# supply.net
KiCad netlist of a schematic drawn in EAGLE
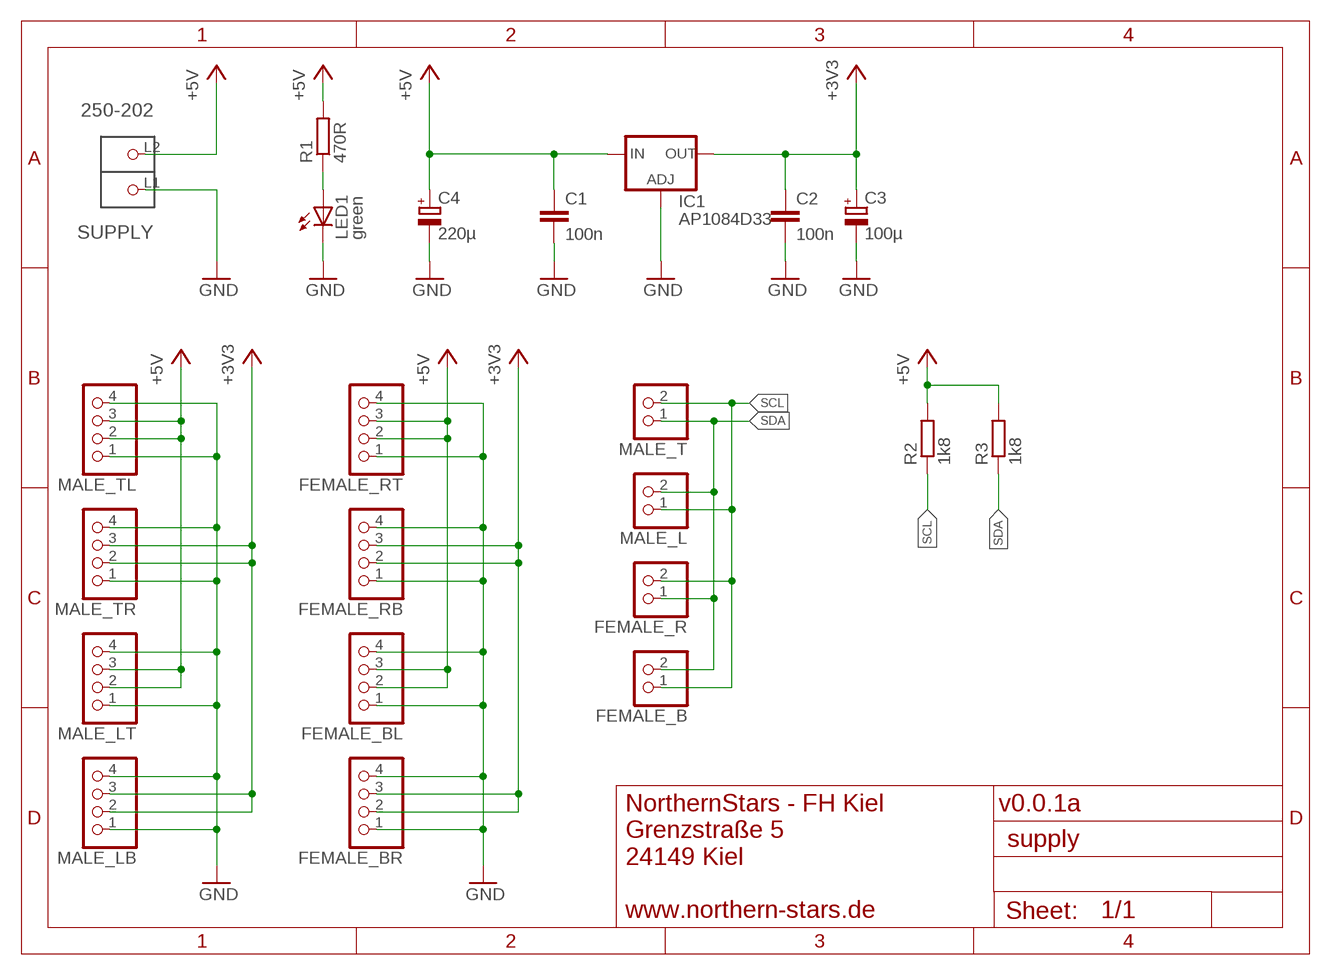
[diagram p0: schematic, sheet 1]

(export (version "E")
  (design (tool "Eeschema 10.0.6"))
  (components
    (comp (ref "C1")
      (value "100n")
      (footprint "eagle-import:C1206")
      (libsource (lib "eagle-import") (part "C-EUC1206"))
    )
    (comp (ref "C2")
      (value "100n")
      (footprint "eagle-import:C1206")
      (libsource (lib "eagle-import") (part "C-EUC1206"))
    )
    (comp (ref "C3")
      (value "100µ")
      (footprint "eagle-import:UD-6,3X5,8_NICHICON")
      (libsource (lib "eagle-import") (part "CPOL-EUUD-6,3X8,8"))
    )
    (comp (ref "C4")
      (value "220µ")
      (footprint "eagle-import:UD-6,3X7,7_NICHICON")
      (libsource (lib "eagle-import") (part "CPOL-EUUD-6,3X7,7"))
    )
    (comp (ref "FEMALE_B")
      (value "PINHD-1X02_2.54-90°")
      (footprint "eagle-import:1X02_90")
      (libsource (lib "eagle-import") (part "PINHD-1X02_2.54-90°"))
    )
    (comp (ref "FEMALE_BL")
      (value "PINHD-1X04_2.54-90°")
      (footprint "eagle-import:1X04_90")
      (libsource (lib "eagle-import") (part "PINHD-1X04_2.54-90°"))
    )
    (comp (ref "FEMALE_BR")
      (value "PINHD-1X04_2.54-90°")
      (footprint "eagle-import:1X04_90")
      (libsource (lib "eagle-import") (part "PINHD-1X04_2.54-90°"))
    )
    (comp (ref "FEMALE_R")
      (value "PINHD-1X02_2.54-90°")
      (footprint "eagle-import:1X02_90")
      (libsource (lib "eagle-import") (part "PINHD-1X02_2.54-90°"))
    )
    (comp (ref "FEMALE_RB")
      (value "PINHD-1X04_2.54-90°")
      (footprint "eagle-import:1X04_90")
      (libsource (lib "eagle-import") (part "PINHD-1X04_2.54-90°"))
    )
    (comp (ref "FEMALE_RT")
      (value "PINHD-1X04_2.54-90°")
      (footprint "eagle-import:1X04_90")
      (libsource (lib "eagle-import") (part "PINHD-1X04_2.54-90°"))
    )
    (comp (ref "IC1")
      (value "AP1084D33")
      (footprint "eagle-import:TO252")
      (libsource (lib "eagle-import") (part "AP1084"))
    )
    (comp (ref "LED1")
      (value "green")
      (footprint "eagle-import:CHIPLED_1206")
      (libsource (lib "eagle-import") (part "LEDCHIPLED_1206"))
    )
    (comp (ref "MALE_L")
      (value "PINHD-1X02_2.54-90°")
      (footprint "eagle-import:1X02_90")
      (libsource (lib "eagle-import") (part "PINHD-1X02_2.54-90°"))
    )
    (comp (ref "MALE_LB")
      (value "PINHD-1X04_2.54-90°")
      (footprint "eagle-import:1X04_90")
      (libsource (lib "eagle-import") (part "PINHD-1X04_2.54-90°"))
    )
    (comp (ref "MALE_LT")
      (value "PINHD-1X04_2.54-90°")
      (footprint "eagle-import:1X04_90")
      (libsource (lib "eagle-import") (part "PINHD-1X04_2.54-90°"))
    )
    (comp (ref "MALE_T")
      (value "PINHD-1X02_2.54-90°")
      (footprint "eagle-import:1X02_90")
      (libsource (lib "eagle-import") (part "PINHD-1X02_2.54-90°"))
    )
    (comp (ref "MALE_TL")
      (value "PINHD-1X04_2.54-90°")
      (footprint "eagle-import:1X04_90")
      (libsource (lib "eagle-import") (part "PINHD-1X04_2.54-90°"))
    )
    (comp (ref "MALE_TR")
      (value "PINHD-1X04_2.54-90°")
      (footprint "eagle-import:1X04_90")
      (libsource (lib "eagle-import") (part "PINHD-1X04_2.54-90°"))
    )
    (comp (ref "R1")
      (value "470R")
      (footprint "eagle-import:R1206")
      (libsource (lib "eagle-import") (part "R-EU_R1206"))
    )
    (comp (ref "R2")
      (value "1k8")
      (footprint "eagle-import:R1206")
      (libsource (lib "eagle-import") (part "R-EU_R1206"))
    )
    (comp (ref "R3")
      (value "1k8")
      (footprint "eagle-import:R1206")
      (libsource (lib "eagle-import") (part "R-EU_R1206"))
    )
    (comp (ref "SUPPLY")
      (value "250-202")
      (footprint "eagle-import:P-250-202")
      (libsource (lib "eagle-import") (part "250-202"))
    )
  )
  (nets
    (net (code "1") (name "+3V3") (class "Default")
      (node (ref "C2") (pin "1") (pinfunction "1_1") (pintype "passive"))
      (node (ref "C3") (pin "+") (pinfunction "+_+") (pintype "passive"))
      (node (ref "FEMALE_BR") (pin "2") (pinfunction "2_2") (pintype "passive"))
      (node (ref "FEMALE_BR") (pin "3") (pinfunction "3_3") (pintype "passive"))
      (node (ref "FEMALE_RB") (pin "2") (pinfunction "2_2") (pintype "passive"))
      (node (ref "FEMALE_RB") (pin "3") (pinfunction "3_3") (pintype "passive"))
      (node (ref "IC1") (pin "3") (pinfunction "OUT_3") (pintype "passive"))
      (node (ref "MALE_LB") (pin "2") (pinfunction "2_2") (pintype "passive"))
      (node (ref "MALE_LB") (pin "3") (pinfunction "3_3") (pintype "passive"))
      (node (ref "MALE_TR") (pin "2") (pinfunction "2_2") (pintype "passive"))
      (node (ref "MALE_TR") (pin "3") (pinfunction "3_3") (pintype "passive"))
    )
    (net (code "2") (name "+5V") (class "Default")
      (node (ref "C1") (pin "1") (pinfunction "1_1") (pintype "passive"))
      (node (ref "C4") (pin "+") (pinfunction "+_+") (pintype "passive"))
      (node (ref "FEMALE_BL") (pin "2") (pinfunction "2_2") (pintype "passive"))
      (node (ref "FEMALE_BL") (pin "3") (pinfunction "3_3") (pintype "passive"))
      (node (ref "FEMALE_RT") (pin "2") (pinfunction "2_2") (pintype "passive"))
      (node (ref "FEMALE_RT") (pin "3") (pinfunction "3_3") (pintype "passive"))
      (node (ref "IC1") (pin "2") (pinfunction "IN_2") (pintype "input"))
      (node (ref "MALE_LT") (pin "2") (pinfunction "2_2") (pintype "passive"))
      (node (ref "MALE_LT") (pin "3") (pinfunction "3_3") (pintype "passive"))
      (node (ref "MALE_TL") (pin "2") (pinfunction "2_2") (pintype "passive"))
      (node (ref "MALE_TL") (pin "3") (pinfunction "3_3") (pintype "passive"))
      (node (ref "R1") (pin "2") (pinfunction "2_2") (pintype "passive"))
      (node (ref "R2") (pin "2") (pinfunction "2_2") (pintype "passive"))
      (node (ref "R3") (pin "2") (pinfunction "2_2") (pintype "passive"))
      (node (ref "SUPPLY") (pin "L2") (pinfunction "P2_L2") (pintype "bidirectional"))
    )
    (net (code "3") (name "GND") (class "Default")
      (node (ref "C1") (pin "2") (pinfunction "2_2") (pintype "passive"))
      (node (ref "C2") (pin "2") (pinfunction "2_2") (pintype "passive"))
      (node (ref "C3") (pin "-") (pinfunction "-_-") (pintype "passive"))
      (node (ref "C4") (pin "-") (pinfunction "-_-") (pintype "passive"))
      (node (ref "FEMALE_BL") (pin "1") (pinfunction "1_1") (pintype "passive"))
      (node (ref "FEMALE_BL") (pin "4") (pinfunction "4_4") (pintype "passive"))
      (node (ref "FEMALE_BR") (pin "1") (pinfunction "1_1") (pintype "passive"))
      (node (ref "FEMALE_BR") (pin "4") (pinfunction "4_4") (pintype "passive"))
      (node (ref "FEMALE_RB") (pin "1") (pinfunction "1_1") (pintype "passive"))
      (node (ref "FEMALE_RB") (pin "4") (pinfunction "4_4") (pintype "passive"))
      (node (ref "FEMALE_RT") (pin "1") (pinfunction "1_1") (pintype "passive"))
      (node (ref "FEMALE_RT") (pin "4") (pinfunction "4_4") (pintype "passive"))
      (node (ref "IC1") (pin "1") (pinfunction "ADJ_1") (pintype "input"))
      (node (ref "LED1") (pin "C") (pinfunction "C_C") (pintype "passive"))
      (node (ref "MALE_LB") (pin "1") (pinfunction "1_1") (pintype "passive"))
      (node (ref "MALE_LB") (pin "4") (pinfunction "4_4") (pintype "passive"))
      (node (ref "MALE_LT") (pin "1") (pinfunction "1_1") (pintype "passive"))
      (node (ref "MALE_LT") (pin "4") (pinfunction "4_4") (pintype "passive"))
      (node (ref "MALE_TL") (pin "1") (pinfunction "1_1") (pintype "passive"))
      (node (ref "MALE_TL") (pin "4") (pinfunction "4_4") (pintype "passive"))
      (node (ref "MALE_TR") (pin "1") (pinfunction "1_1") (pintype "passive"))
      (node (ref "MALE_TR") (pin "4") (pinfunction "4_4") (pintype "passive"))
      (node (ref "SUPPLY") (pin "L1") (pinfunction "P1_L1") (pintype "bidirectional"))
    )
    (net (code "4") (name "Net-(LED1-PadA)") (class "Default")
      (node (ref "LED1") (pin "A") (pinfunction "A_A") (pintype "passive"))
      (node (ref "R1") (pin "1") (pinfunction "1_1") (pintype "passive"))
    )
    (net (code "5") (name "SCL") (class "Default")
      (node (ref "FEMALE_B") (pin "1") (pinfunction "1_1") (pintype "passive"))
      (node (ref "FEMALE_R") (pin "2") (pinfunction "2_2") (pintype "passive"))
      (node (ref "MALE_L") (pin "1") (pinfunction "1_1") (pintype "passive"))
      (node (ref "MALE_T") (pin "2") (pinfunction "2_2") (pintype "passive"))
      (node (ref "R2") (pin "1") (pinfunction "1_1") (pintype "passive"))
    )
    (net (code "6") (name "SDA") (class "Default")
      (node (ref "FEMALE_B") (pin "2") (pinfunction "2_2") (pintype "passive"))
      (node (ref "FEMALE_R") (pin "1") (pinfunction "1_1") (pintype "passive"))
      (node (ref "MALE_L") (pin "2") (pinfunction "2_2") (pintype "passive"))
      (node (ref "MALE_T") (pin "1") (pinfunction "1_1") (pintype "passive"))
      (node (ref "R3") (pin "1") (pinfunction "1_1") (pintype "passive"))
    )
  )
)
